# Sheet3.net
KiCad netlist of a schematic drawn in Altium Designer
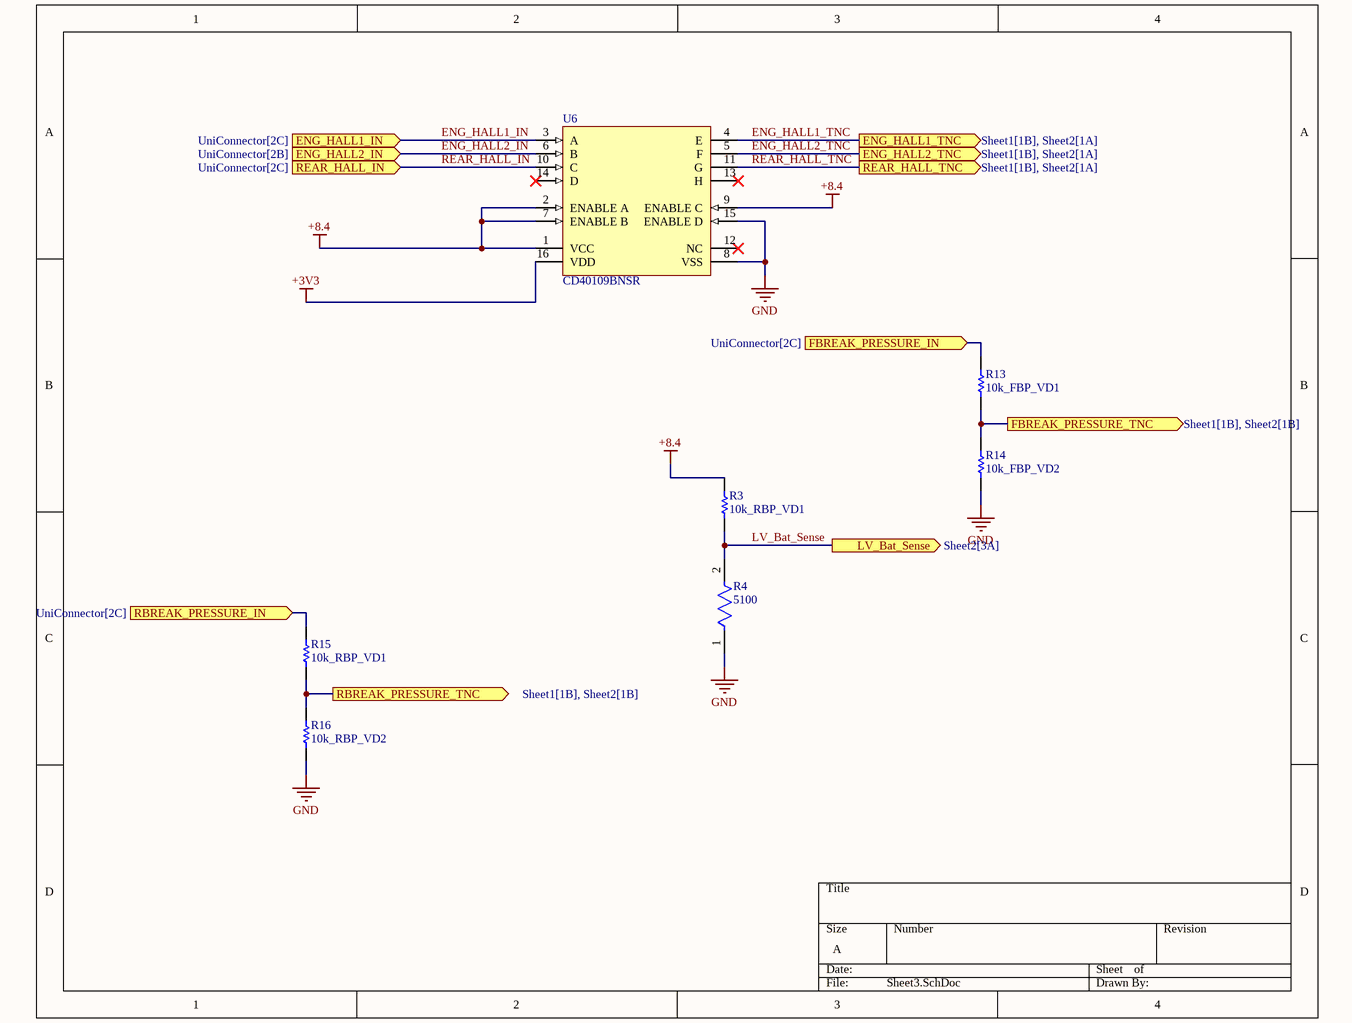
[diagram p0: Sheet3.SchDoc]

(export (version "E")
  (design (tool "Eeschema 10.0.6"))
  (components
    (comp (ref "R3")
      (value "10k_RBP_VD1")
      (footprint "RESC2013X60X40LL20T25")
      (fields (field (name "MANUFACTURER") "Panasonic") (field (name "PART NUMBER") "ERA6AEB7870V"))
      (libsource (lib "Altium Content Vault") (part "RES"))
    )
    (comp (ref "R4")
      (value "5100")
      (footprint "FP-CRCW0805-e3-MFG")
      (description "RES Thick Film, 5.1kΩ, 1%, 0.125W, 100ppm/°C, 0805 CRCW08055K10FKEA")
      (fields (field (name "TOLERANCE") "1%"))
      (libsource (lib "Altium Content Vault") (part "1029c3af85768c4190bb7ad29bc67b5"))
    )
    (comp (ref "R13")
      (value "10k_FBP_VD1")
      (footprint "RESC2013X60X40LL20T25")
      (fields (field (name "MANUFACTURER") "Panasonic") (field (name "PART NUMBER") "ERA6AEB7870V"))
      (libsource (lib "Altium Content Vault") (part "RES"))
    )
    (comp (ref "R14")
      (value "10k_FBP_VD2")
      (footprint "RESC2013X60X40LL20T25")
      (fields (field (name "MANUFACTURER") "Panasonic") (field (name "PART NUMBER") "ERA6AEB7870V"))
      (libsource (lib "Altium Content Vault") (part "RES"))
    )
    (comp (ref "R15")
      (value "10k_RBP_VD1")
      (footprint "RESC2013X60X40LL20T25")
      (fields (field (name "MANUFACTURER") "Panasonic") (field (name "PART NUMBER") "ERA6AEB7870V"))
      (libsource (lib "Altium Content Vault") (part "RES"))
    )
    (comp (ref "R16")
      (value "10k_RBP_VD2")
      (footprint "RESC2013X60X40LL20T25")
      (fields (field (name "MANUFACTURER") "Panasonic") (field (name "PART NUMBER") "ERA6AEB7870V"))
      (libsource (lib "Altium Content Vault") (part "RES"))
    )
    (comp (ref "U6")
      (value "CD40109BNSR")
      (footprint "NS0016A_N")
      (fields (field (name "MANUFACTURER") "Texas Instruments"))
      (libsource (lib "Altium Content Vault") (part "TI-CD40109B-16"))
    )
  )
  (nets
    (net (code "1") (name "+3V3") (class "Default")
      (node (ref "U6") (pin "16") (pinfunction "VDD_16") (pintype "power_in"))
    )
    (net (code "2") (name "+8.4") (class "Default")
      (node (ref "R3") (pin "2") (pinfunction "2_2") (pintype "passive"))
      (node (ref "U6") (pin "1") (pinfunction "VCC_1") (pintype "power_in"))
      (node (ref "U6") (pin "2") (pinfunction "ENABLE_A_2") (pintype "input"))
      (node (ref "U6") (pin "7") (pinfunction "ENABLE_B_7") (pintype "input"))
      (node (ref "U6") (pin "9") (pinfunction "ENABLE_C_9") (pintype "input"))
    )
    (net (code "3") (name "/ENG_HALL1_IN") (class "Default")
      (node (ref "U6") (pin "3") (pinfunction "A_3") (pintype "input"))
    )
    (net (code "4") (name "/ENG_HALL1_TNC") (class "Default")
      (node (ref "U6") (pin "4") (pinfunction "E_4") (pintype "tri_state"))
    )
    (net (code "5") (name "/ENG_HALL2_IN") (class "Default")
      (node (ref "U6") (pin "6") (pinfunction "B_6") (pintype "input"))
    )
    (net (code "6") (name "/ENG_HALL2_TNC") (class "Default")
      (node (ref "U6") (pin "5") (pinfunction "F_5") (pintype "tri_state"))
    )
    (net (code "7") (name "/FBREAK_PRESSURE_IN") (class "Default")
      (node (ref "R13") (pin "2") (pinfunction "2_2") (pintype "passive"))
    )
    (net (code "8") (name "/FBREAK_PRESSURE_TNC") (class "Default")
      (node (ref "R13") (pin "1") (pinfunction "1_1") (pintype "passive"))
      (node (ref "R14") (pin "2") (pinfunction "2_2") (pintype "passive"))
    )
    (net (code "9") (name "/LV_Bat_Sense") (class "Default")
      (node (ref "R3") (pin "1") (pinfunction "1_1") (pintype "passive"))
      (node (ref "R4") (pin "2") (pinfunction "2_2") (pintype "passive"))
    )
    (net (code "10") (name "/RBREAK_PRESSURE_IN") (class "Default")
      (node (ref "R15") (pin "2") (pinfunction "2_2") (pintype "passive"))
    )
    (net (code "11") (name "/RBREAK_PRESSURE_TNC") (class "Default")
      (node (ref "R15") (pin "1") (pinfunction "1_1") (pintype "passive"))
      (node (ref "R16") (pin "2") (pinfunction "2_2") (pintype "passive"))
    )
    (net (code "12") (name "/REAR_HALL_IN") (class "Default")
      (node (ref "U6") (pin "10") (pinfunction "C_10") (pintype "input"))
    )
    (net (code "13") (name "/REAR_HALL_TNC") (class "Default")
      (node (ref "U6") (pin "11") (pinfunction "G_11") (pintype "tri_state"))
    )
    (net (code "14") (name "GND") (class "Default")
      (node (ref "R14") (pin "1") (pinfunction "1_1") (pintype "passive"))
      (node (ref "R16") (pin "1") (pinfunction "1_1") (pintype "passive"))
      (node (ref "R4") (pin "1") (pinfunction "1_1") (pintype "passive"))
      (node (ref "U6") (pin "15") (pinfunction "ENABLE_D_15") (pintype "input"))
      (node (ref "U6") (pin "8") (pinfunction "VSS_8") (pintype "power_in"))
    )
    (net (code "15") (name "unconnected-(U6-D-Pad14)") (class "Default")
      (node (ref "U6") (pin "14") (pinfunction "D_14") (pintype "input+no_connect"))
    )
    (net (code "16") (name "unconnected-(U6-H-Pad13)") (class "Default")
      (node (ref "U6") (pin "13") (pinfunction "H_13") (pintype "tri_state+no_connect"))
    )
    (net (code "17") (name "unconnected-(U6-NC-Pad12)") (class "Default")
      (node (ref "U6") (pin "12") (pinfunction "NC_12") (pintype "passive+no_connect"))
    )
  )
)
